# pocket_avr_programmer_to_atmega_328p.net
KiCad netlist of a schematic drawn in EAGLE
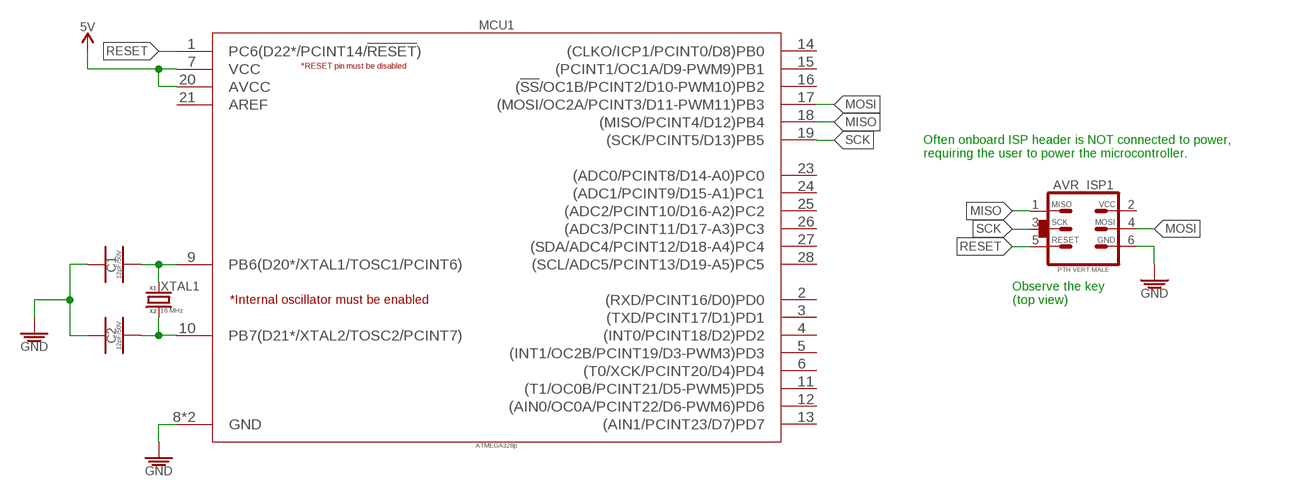
[diagram p0: schematic, sheet 1]

(export (version "E")
  (design (tool "Eeschema 10.0.6"))
  (components
    (comp (ref "AVR_ISP1")
      (value "PTH VERT MALE")
      (footprint "eagle-import:HDRV6W64P254_2X3_762X483X838B_AVR-ISP")
      (fields (field (name "MFR") "Amphenol FCI") (field (name "MPN") "67997-206HLF"))
      (libsource (lib "eagle-import") (part "AVR_SPI_PRG_6_PTH_VERT_MALE_2.54MM"))
    )
    (comp (ref "C1")
      (value "12pF/50V")
      (footprint "eagle-import:_CER_PTH_LS2.5_L4-W2.5-H5.58")
      (fields (field (name "MFR") "Vishay BC Components") (field (name "MPN") "K120J15C0GF5TL2"))
      (libsource (lib "eagle-import") (part "12PF_PTH-CER_50V-5%"))
    )
    (comp (ref "C2")
      (value "12pF/50V")
      (footprint "eagle-import:_CER_PTH_LS2.5_L4-W2.5-H5.58")
      (fields (field (name "MFR") "Vishay BC Components") (field (name "MPN") "K120J15C0GF5TL2"))
      (libsource (lib "eagle-import") (part "12PF_PTH-CER_50V-5%"))
    )
    (comp (ref "MCU1")
      (value "ATMEGA328p")
      (footprint "eagle-import:DIP762W53P254L3467H472Q28B")
      (fields (field (name "MFR") "Microchip Technology") (field (name "MPN") "ATMEGA328P-PU"))
      (libsource (lib "eagle-import") (part "ATMEGA328P-28_28-PDIP_8BIT_32KB"))
    )
    (comp (ref "XTAL1")
      (value "16 MHz")
      (footprint "eagle-import:HC-49_US")
      (fields (field (name "MFR") "Abracon LLC") (field (name "MPN") "ABL-16.000MHZ-B2"))
      (libsource (lib "eagle-import") (part "CRYSTAL_ABL_16MHZ_18PF"))
    )
  )
  (nets
    (net (code "1") (name "5V") (class "Default")
      (node (ref "MCU1") (pin "20") (pinfunction "AVCC_20") (pintype "power_in"))
      (node (ref "MCU1") (pin "7") (pinfunction "VCC_7") (pintype "power_in"))
    )
    (net (code "2") (name "GND") (class "Default")
      (node (ref "AVR_ISP1") (pin "GND") (pinfunction "GND_GND") (pintype "power_in"))
      (node (ref "C1") (pin "P$1") (pinfunction "1_P$1") (pintype "passive"))
      (node (ref "C2") (pin "P$1") (pinfunction "1_P$1") (pintype "passive"))
      (node (ref "MCU1") (pin "22") (pinfunction "GND_22") (pintype "power_in"))
      (node (ref "MCU1") (pin "8") (pinfunction "GND_8") (pintype "power_in"))
    )
    (net (code "3") (name "MISO") (class "Default")
      (node (ref "AVR_ISP1") (pin "MISO") (pinfunction "MISO_MISO") (pintype "bidirectional"))
      (node (ref "MCU1") (pin "18") (pinfunction "(MISO/PCINT4/D12)PB4_18") (pintype "bidirectional"))
    )
    (net (code "4") (name "MOSI") (class "Default")
      (node (ref "AVR_ISP1") (pin "MOSI") (pinfunction "MOSI_MOSI") (pintype "bidirectional"))
      (node (ref "MCU1") (pin "17") (pinfunction "(MOSI/OC2A/PCINT3/D11-PWM11)PB3_17") (pintype "bidirectional"))
    )
    (net (code "5") (name "Net-(C1-2)") (class "Default")
      (node (ref "C1") (pin "P$2") (pinfunction "2_P$2") (pintype "passive"))
      (node (ref "MCU1") (pin "9") (pinfunction "PB6(D20*/XTAL1/TOSC1/PCINT6)_9") (pintype "bidirectional"))
      (node (ref "XTAL1") (pin "P$1") (pinfunction "XTAL1_P$1") (pintype "passive"))
    )
    (net (code "6") (name "Net-(C2-2)") (class "Default")
      (node (ref "C2") (pin "P$2") (pinfunction "2_P$2") (pintype "passive"))
      (node (ref "MCU1") (pin "10") (pinfunction "PB7(D21*/XTAL2/TOSC2/PCINT7)_10") (pintype "bidirectional"))
      (node (ref "XTAL1") (pin "P$2") (pinfunction "XTAL2_P$2") (pintype "passive"))
    )
    (net (code "7") (name "RESET") (class "Default")
      (node (ref "AVR_ISP1") (pin "RESET") (pinfunction "RESET_RESET") (pintype "bidirectional"))
      (node (ref "MCU1") (pin "1") (pinfunction "PC6(D22*/PCINT14/~{RESET})_1") (pintype "bidirectional"))
    )
    (net (code "8") (name "SCK") (class "Default")
      (node (ref "AVR_ISP1") (pin "SCK") (pinfunction "SCK_SCK") (pintype "bidirectional"))
      (node (ref "MCU1") (pin "19") (pinfunction "(SCK/PCINT5/D13)PB5_19") (pintype "bidirectional"))
    )
    (net (code "9") (name "unconnected-(AVR_ISP1-PadVCC)") (class "Default")
      (node (ref "AVR_ISP1") (pin "VCC") (pinfunction "VCC_VCC") (pintype "no_connect"))
    )
    (net (code "10") (name "unconnected-(MCU1-(ADC0{slash}PCINT8{slash}D14-A0)PC0-Pad23)") (class "Default")
      (node (ref "MCU1") (pin "23") (pinfunction "(ADC0/PCINT8/D14-A0)PC0_23") (pintype "bidirectional"))
    )
    (net (code "11") (name "unconnected-(MCU1-(ADC1{slash}PCINT9{slash}D15-A1)PC1-Pad24)") (class "Default")
      (node (ref "MCU1") (pin "24") (pinfunction "(ADC1/PCINT9/D15-A1)PC1_24") (pintype "bidirectional"))
    )
    (net (code "12") (name "unconnected-(MCU1-(ADC2{slash}PCINT10{slash}D16-A2)PC2-Pad25)") (class "Default")
      (node (ref "MCU1") (pin "25") (pinfunction "(ADC2/PCINT10/D16-A2)PC2_25") (pintype "bidirectional"))
    )
    (net (code "13") (name "unconnected-(MCU1-(ADC3{slash}PCINT11{slash}D17-A3)PC3-Pad26)") (class "Default")
      (node (ref "MCU1") (pin "26") (pinfunction "(ADC3/PCINT11/D17-A3)PC3_26") (pintype "bidirectional"))
    )
    (net (code "14") (name "unconnected-(MCU1-(AIN0{slash}OC0A{slash}PCINT22{slash}D6-PWM6)PD6-Pad12)") (class "Default")
      (node (ref "MCU1") (pin "12") (pinfunction "(AIN0/OC0A/PCINT22/D6-PWM6)PD6_12") (pintype "bidirectional"))
    )
    (net (code "15") (name "unconnected-(MCU1-(AIN1{slash}PCINT23{slash}D7)PD7-Pad13)") (class "Default")
      (node (ref "MCU1") (pin "13") (pinfunction "(AIN1/PCINT23/D7)PD7_13") (pintype "bidirectional"))
    )
    (net (code "16") (name "unconnected-(MCU1-(CLKO{slash}ICP1{slash}PCINT0{slash}D8)PB0-Pad14)") (class "Default")
      (node (ref "MCU1") (pin "14") (pinfunction "(CLKO/ICP1/PCINT0/D8)PB0_14") (pintype "bidirectional"))
    )
    (net (code "17") (name "unconnected-(MCU1-(INT0{slash}PCINT18{slash}D2)PD2-Pad4)") (class "Default")
      (node (ref "MCU1") (pin "4") (pinfunction "(INT0/PCINT18/D2)PD2_4") (pintype "bidirectional"))
    )
    (net (code "18") (name "unconnected-(MCU1-(INT1{slash}OC2B{slash}PCINT19{slash}D3-PWM3)PD3-Pad5)") (class "Default")
      (node (ref "MCU1") (pin "5") (pinfunction "(INT1/OC2B/PCINT19/D3-PWM3)PD3_5") (pintype "bidirectional"))
    )
    (net (code "19") (name "unconnected-(MCU1-(PCINT1{slash}OC1A{slash}D9-PWM9)PB1-Pad15)") (class "Default")
      (node (ref "MCU1") (pin "15") (pinfunction "(PCINT1/OC1A/D9-PWM9)PB1_15") (pintype "bidirectional"))
    )
    (net (code "20") (name "unconnected-(MCU1-(RXD{slash}PCINT16{slash}D0)PD0-Pad2)") (class "Default")
      (node (ref "MCU1") (pin "2") (pinfunction "(RXD/PCINT16/D0)PD0_2") (pintype "bidirectional"))
    )
    (net (code "21") (name "unconnected-(MCU1-(SCL{slash}ADC5{slash}PCINT13{slash}D19-A5)PC5-Pad28)") (class "Default")
      (node (ref "MCU1") (pin "28") (pinfunction "(SCL/ADC5/PCINT13/D19-A5)PC5_28") (pintype "bidirectional"))
    )
    (net (code "22") (name "unconnected-(MCU1-(SDA{slash}ADC4{slash}PCINT12{slash}D18-A4)PC4-Pad27)") (class "Default")
      (node (ref "MCU1") (pin "27") (pinfunction "(SDA/ADC4/PCINT12/D18-A4)PC4_27") (pintype "bidirectional"))
    )
    (net (code "23") (name "unconnected-(MCU1-(T0{slash}XCK{slash}PCINT20{slash}D4)PD4-Pad6)") (class "Default")
      (node (ref "MCU1") (pin "6") (pinfunction "(T0/XCK/PCINT20/D4)PD4_6") (pintype "bidirectional"))
    )
    (net (code "24") (name "unconnected-(MCU1-(T1{slash}OC0B{slash}PCINT21{slash}D5-PWM5)PD5-Pad11)") (class "Default")
      (node (ref "MCU1") (pin "11") (pinfunction "(T1/OC0B/PCINT21/D5-PWM5)PD5_11") (pintype "bidirectional"))
    )
    (net (code "25") (name "unconnected-(MCU1-(TXD{slash}PCINT17{slash}D1)PD1-Pad3)") (class "Default")
      (node (ref "MCU1") (pin "3") (pinfunction "(TXD/PCINT17/D1)PD1_3") (pintype "bidirectional"))
    )
    (net (code "26") (name "unconnected-(MCU1-(~{SS}{slash}OC1B{slash}PCINT2{slash}D10-PWM10)PB2-Pad16)") (class "Default")
      (node (ref "MCU1") (pin "16") (pinfunction "(~{SS}/OC1B/PCINT2/D10-PWM10)PB2_16") (pintype "bidirectional"))
    )
    (net (code "27") (name "unconnected-(MCU1-AREF-Pad21)") (class "Default")
      (node (ref "MCU1") (pin "21") (pinfunction "AREF_21") (pintype "passive"))
    )
  )
)
